# Snake.net
KiCad netlist of a schematic drawn in EAGLE
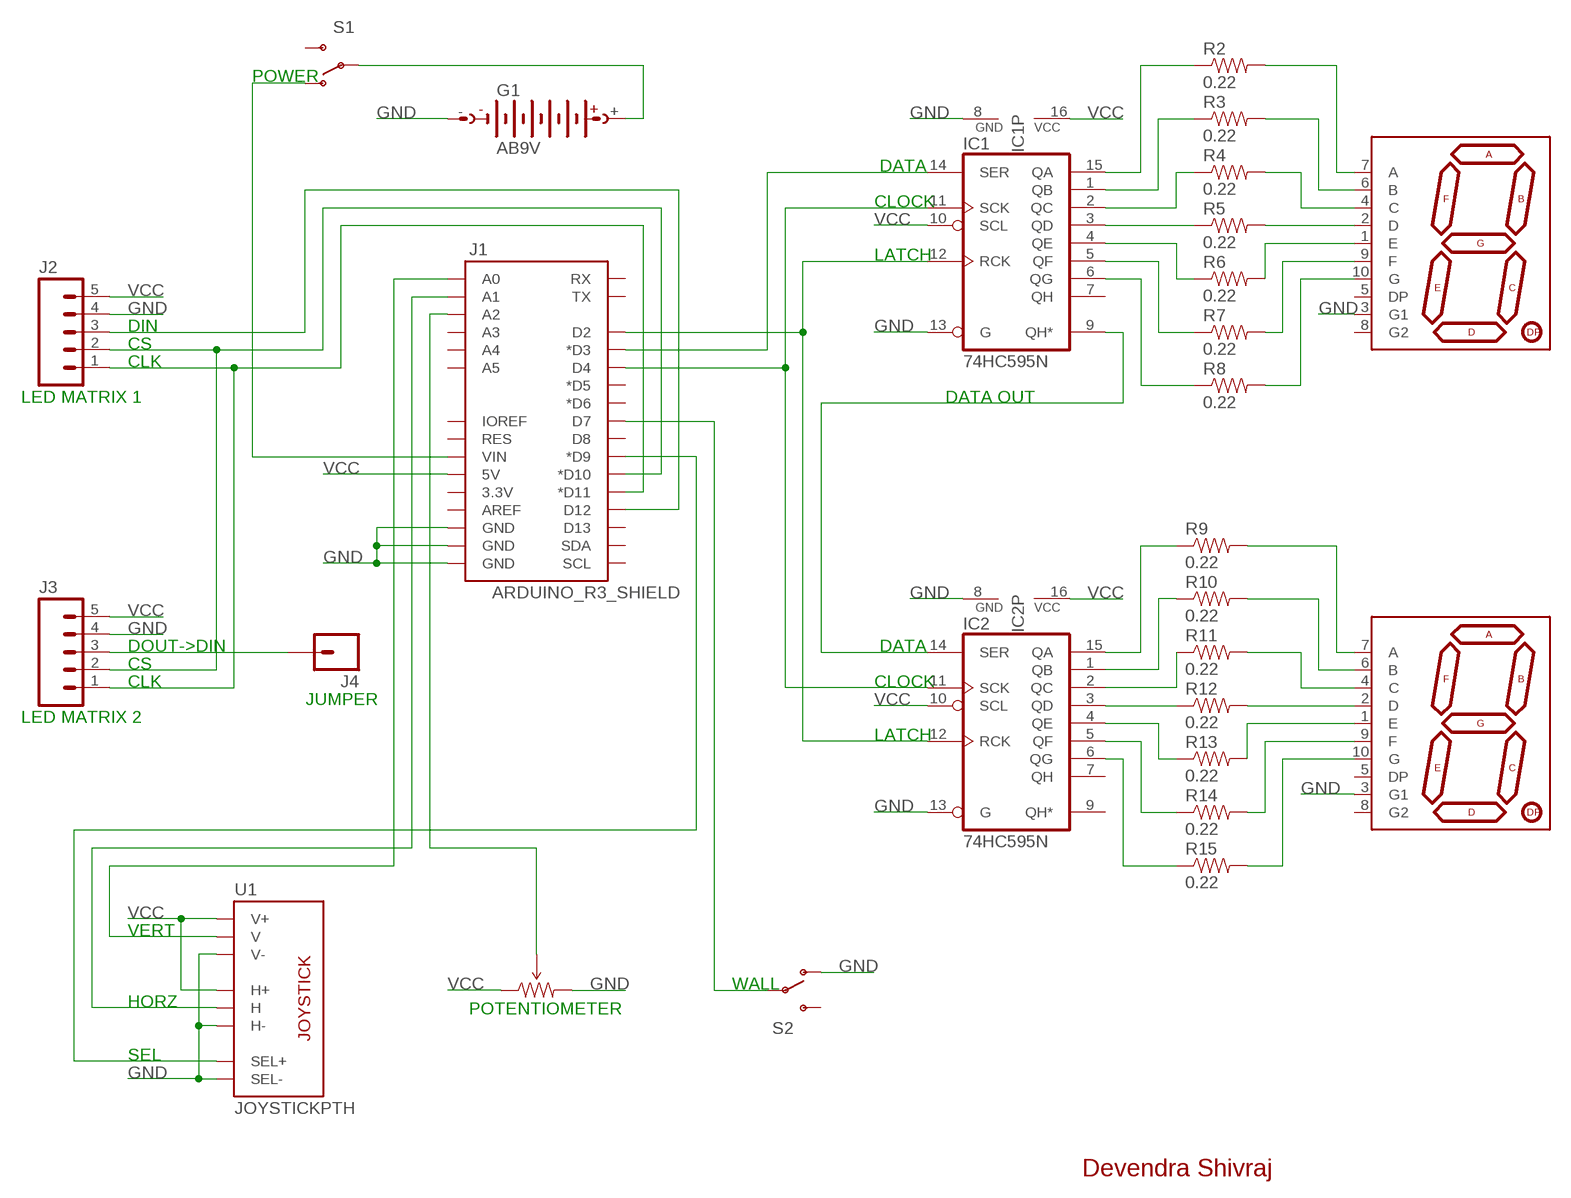
[diagram p0: schematic, sheet 1]

(export (version "E")
  (design (tool "Eeschema 10.0.6"))
  (components
    (comp (ref "G1")
      (value "AB9V")
      (footprint "eagle-import:AB9V")
      (libsource (lib "eagle-import") (part "AB9V"))
    )
    (comp (ref "IC1")
      (value "74HC595N")
      (footprint "eagle-import:DIL16")
      (libsource (lib "eagle-import") (part "74595NHC"))
    )
    (comp (ref "IC2")
      (value "74HC595N")
      (footprint "eagle-import:DIL16")
      (libsource (lib "eagle-import") (part "74595NHC"))
    )
    (comp (ref "J1")
      (value "ARDUINO_R3_SHIELD")
      (footprint "eagle-import:UNO_R3_SHIELD")
      (libsource (lib "eagle-import") (part "ARDUINO_R3_SHIELD"))
    )
    (comp (ref "J2")
      (value "M05PTH")
      (footprint "eagle-import:1X05")
      (libsource (lib "eagle-import") (part "M05PTH"))
    )
    (comp (ref "J3")
      (value "M05PTH")
      (footprint "eagle-import:1X05")
      (libsource (lib "eagle-import") (part "M05PTH"))
    )
    (comp (ref "J4")
      (value "M01PTH")
      (footprint "eagle-import:1X01")
      (libsource (lib "eagle-import") (part "M01PTH"))
    )
    (comp (ref "R1")
      (value "TSR-3386")
      (footprint "eagle-import:3386U")
      (libsource (lib "eagle-import") (part "TRIMPOT-PTH-KNOB"))
    )
    (comp (ref "R2")
      (value "0.22")
      (footprint "eagle-import:0805")
      (libsource (lib "eagle-import") (part "0.22OHM-1/4W-1%(0805)"))
    )
    (comp (ref "R3")
      (value "0.22")
      (footprint "eagle-import:0805")
      (libsource (lib "eagle-import") (part "0.22OHM-1/4W-1%(0805)"))
    )
    (comp (ref "R4")
      (value "0.22")
      (footprint "eagle-import:0805")
      (libsource (lib "eagle-import") (part "0.22OHM-1/4W-1%(0805)"))
    )
    (comp (ref "R5")
      (value "0.22")
      (footprint "eagle-import:0805")
      (libsource (lib "eagle-import") (part "0.22OHM-1/4W-1%(0805)"))
    )
    (comp (ref "R6")
      (value "0.22")
      (footprint "eagle-import:0805")
      (libsource (lib "eagle-import") (part "0.22OHM-1/4W-1%(0805)"))
    )
    (comp (ref "R7")
      (value "0.22")
      (footprint "eagle-import:0805")
      (libsource (lib "eagle-import") (part "0.22OHM-1/4W-1%(0805)"))
    )
    (comp (ref "R8")
      (value "0.22")
      (footprint "eagle-import:0805")
      (libsource (lib "eagle-import") (part "0.22OHM-1/4W-1%(0805)"))
    )
    (comp (ref "R9")
      (value "0.22")
      (footprint "eagle-import:0805")
      (libsource (lib "eagle-import") (part "0.22OHM-1/4W-1%(0805)"))
    )
    (comp (ref "R10")
      (value "0.22")
      (footprint "eagle-import:0805")
      (libsource (lib "eagle-import") (part "0.22OHM-1/4W-1%(0805)"))
    )
    (comp (ref "R11")
      (value "0.22")
      (footprint "eagle-import:0805")
      (libsource (lib "eagle-import") (part "0.22OHM-1/4W-1%(0805)"))
    )
    (comp (ref "R12")
      (value "0.22")
      (footprint "eagle-import:0805")
      (libsource (lib "eagle-import") (part "0.22OHM-1/4W-1%(0805)"))
    )
    (comp (ref "R13")
      (value "0.22")
      (footprint "eagle-import:0805")
      (libsource (lib "eagle-import") (part "0.22OHM-1/4W-1%(0805)"))
    )
    (comp (ref "R14")
      (value "0.22")
      (footprint "eagle-import:0805")
      (libsource (lib "eagle-import") (part "0.22OHM-1/4W-1%(0805)"))
    )
    (comp (ref "R15")
      (value "0.22")
      (footprint "eagle-import:0805")
      (libsource (lib "eagle-import") (part "0.22OHM-1/4W-1%(0805)"))
    )
    (comp (ref "S1")
      (value "SWITCH-SPDTPTH")
      (footprint "eagle-import:SWITCH-SPDT")
      (libsource (lib "eagle-import") (part "SWITCH-SPDTPTH"))
    )
    (comp (ref "S2")
      (value "SWITCH-SPDTPTH")
      (footprint "eagle-import:SWITCH-SPDT")
      (libsource (lib "eagle-import") (part "SWITCH-SPDTPTH"))
    )
    (comp (ref "U$1")
      (value "7-SEGMENT-DISPLAYPTH")
      (footprint "eagle-import:7-SEGMENT-DISPLAY")
      (libsource (lib "eagle-import") (part "7-SEGMENT-DISPLAYPTH"))
    )
    (comp (ref "U$2")
      (value "7-SEGMENT-DISPLAYPTH")
      (footprint "eagle-import:7-SEGMENT-DISPLAY")
      (libsource (lib "eagle-import") (part "7-SEGMENT-DISPLAYPTH"))
    )
    (comp (ref "U1")
      (value "JOYSTICKPTH")
      (footprint "eagle-import:JOYSTICK")
      (libsource (lib "eagle-import") (part "JOYSTICKPTH"))
    )
  )
  (nets
    (net (code "1") (name "/GND") (class "Default")
      (node (ref "G1") (pin "-") (pinfunction "-_-") (pintype "passive"))
      (node (ref "IC1") (pin "13") (pinfunction "G_13") (pintype "input"))
      (node (ref "IC1") (pin "8") (pinfunction "GND_8") (pintype "power_in"))
      (node (ref "IC2") (pin "13") (pinfunction "G_13") (pintype "input"))
      (node (ref "IC2") (pin "8") (pinfunction "GND_8") (pintype "power_in"))
      (node (ref "J1") (pin "GND@0") (pinfunction "GND_GND@0") (pintype "bidirectional"))
      (node (ref "J1") (pin "GND@1") (pinfunction "GND_GND@1") (pintype "bidirectional"))
      (node (ref "J1") (pin "GND@2") (pinfunction "GND_GND@2") (pintype "bidirectional"))
      (node (ref "J2") (pin "4") (pinfunction "4_4") (pintype "passive"))
      (node (ref "J3") (pin "4") (pinfunction "4_4") (pintype "passive"))
      (node (ref "R1") (pin "3") (pinfunction "CW_3") (pintype "passive"))
      (node (ref "S2") (pin "1") (pinfunction "O_1") (pintype "passive"))
      (node (ref "U$1") (pin "3") (pinfunction "G1_3") (pintype "bidirectional"))
      (node (ref "U$2") (pin "3") (pinfunction "G1_3") (pintype "bidirectional"))
      (node (ref "U1") (pin "B2A") (pinfunction "SEL-_B2A") (pintype "bidirectional"))
      (node (ref "U1") (pin "H3") (pinfunction "H-_H3") (pintype "bidirectional"))
      (node (ref "U1") (pin "V3") (pinfunction "V-_V3") (pintype "bidirectional"))
    )
    (net (code "2") (name "/VCC") (class "Default")
      (node (ref "IC1") (pin "10") (pinfunction "SCL_10") (pintype "input"))
      (node (ref "IC1") (pin "16") (pinfunction "VCC_16") (pintype "power_in"))
      (node (ref "IC2") (pin "10") (pinfunction "SCL_10") (pintype "input"))
      (node (ref "IC2") (pin "16") (pinfunction "VCC_16") (pintype "power_in"))
      (node (ref "J1") (pin "5V") (pinfunction "5V_5V") (pintype "bidirectional"))
      (node (ref "J2") (pin "5") (pinfunction "5_5") (pintype "passive"))
      (node (ref "J3") (pin "5") (pinfunction "5_5") (pintype "passive"))
      (node (ref "R1") (pin "1") (pinfunction "CCW_1") (pintype "passive"))
      (node (ref "U1") (pin "H1") (pinfunction "H+_H1") (pintype "bidirectional"))
      (node (ref "U1") (pin "V1") (pinfunction "V+_V1") (pintype "bidirectional"))
    )
    (net (code "3") (name "Net-(IC1A-QA)") (class "Default")
      (node (ref "IC1") (pin "15") (pinfunction "QA_15") (pintype "tri_state"))
      (node (ref "R2") (pin "1") (pinfunction "1_1") (pintype "passive"))
    )
    (net (code "4") (name "Net-(IC1A-QB)") (class "Default")
      (node (ref "IC1") (pin "1") (pinfunction "QB_1") (pintype "tri_state"))
      (node (ref "R3") (pin "1") (pinfunction "1_1") (pintype "passive"))
    )
    (net (code "5") (name "Net-(IC1A-QC)") (class "Default")
      (node (ref "IC1") (pin "2") (pinfunction "QC_2") (pintype "tri_state"))
      (node (ref "R4") (pin "1") (pinfunction "1_1") (pintype "passive"))
    )
    (net (code "6") (name "Net-(IC1A-QD)") (class "Default")
      (node (ref "IC1") (pin "3") (pinfunction "QD_3") (pintype "tri_state"))
      (node (ref "R5") (pin "1") (pinfunction "1_1") (pintype "passive"))
    )
    (net (code "7") (name "Net-(IC1A-QE)") (class "Default")
      (node (ref "IC1") (pin "4") (pinfunction "QE_4") (pintype "tri_state"))
      (node (ref "R6") (pin "1") (pinfunction "1_1") (pintype "passive"))
    )
    (net (code "8") (name "Net-(IC1A-QF)") (class "Default")
      (node (ref "IC1") (pin "5") (pinfunction "QF_5") (pintype "tri_state"))
      (node (ref "R7") (pin "1") (pinfunction "1_1") (pintype "passive"))
    )
    (net (code "9") (name "Net-(IC1A-QG)") (class "Default")
      (node (ref "IC1") (pin "6") (pinfunction "QG_6") (pintype "tri_state"))
      (node (ref "R8") (pin "1") (pinfunction "1_1") (pintype "passive"))
    )
    (net (code "10") (name "Net-(IC1A-QH*)") (class "Default")
      (node (ref "IC1") (pin "9") (pinfunction "QH*_9") (pintype "tri_state"))
      (node (ref "IC2") (pin "14") (pinfunction "SER_14") (pintype "input"))
    )
    (net (code "11") (name "Net-(IC1A-RCK)") (class "Default")
      (node (ref "IC1") (pin "12") (pinfunction "RCK_12") (pintype "input"))
      (node (ref "IC2") (pin "12") (pinfunction "RCK_12") (pintype "input"))
      (node (ref "J1") (pin "D2") (pinfunction "D2_D2") (pintype "bidirectional"))
    )
    (net (code "12") (name "Net-(IC1A-SCK)") (class "Default")
      (node (ref "IC1") (pin "11") (pinfunction "SCK_11") (pintype "input"))
      (node (ref "IC2") (pin "11") (pinfunction "SCK_11") (pintype "input"))
      (node (ref "J1") (pin "D4") (pinfunction "D4_D4") (pintype "bidirectional"))
    )
    (net (code "13") (name "Net-(IC1A-SER)") (class "Default")
      (node (ref "IC1") (pin "14") (pinfunction "SER_14") (pintype "input"))
      (node (ref "J1") (pin "D3") (pinfunction "*D3_D3") (pintype "bidirectional"))
    )
    (net (code "14") (name "Net-(IC2A-QA)") (class "Default")
      (node (ref "IC2") (pin "15") (pinfunction "QA_15") (pintype "tri_state"))
      (node (ref "R9") (pin "1") (pinfunction "1_1") (pintype "passive"))
    )
    (net (code "15") (name "Net-(IC2A-QB)") (class "Default")
      (node (ref "IC2") (pin "1") (pinfunction "QB_1") (pintype "tri_state"))
      (node (ref "R10") (pin "1") (pinfunction "1_1") (pintype "passive"))
    )
    (net (code "16") (name "Net-(IC2A-QC)") (class "Default")
      (node (ref "IC2") (pin "2") (pinfunction "QC_2") (pintype "tri_state"))
      (node (ref "R11") (pin "1") (pinfunction "1_1") (pintype "passive"))
    )
    (net (code "17") (name "Net-(IC2A-QD)") (class "Default")
      (node (ref "IC2") (pin "3") (pinfunction "QD_3") (pintype "tri_state"))
      (node (ref "R12") (pin "1") (pinfunction "1_1") (pintype "passive"))
    )
    (net (code "18") (name "Net-(IC2A-QE)") (class "Default")
      (node (ref "IC2") (pin "4") (pinfunction "QE_4") (pintype "tri_state"))
      (node (ref "R13") (pin "1") (pinfunction "1_1") (pintype "passive"))
    )
    (net (code "19") (name "Net-(IC2A-QF)") (class "Default")
      (node (ref "IC2") (pin "5") (pinfunction "QF_5") (pintype "tri_state"))
      (node (ref "R14") (pin "1") (pinfunction "1_1") (pintype "passive"))
    )
    (net (code "20") (name "Net-(IC2A-QG)") (class "Default")
      (node (ref "IC2") (pin "6") (pinfunction "QG_6") (pintype "tri_state"))
      (node (ref "R15") (pin "1") (pinfunction "1_1") (pintype "passive"))
    )
    (net (code "21") (name "Net-(J1-*D9)") (class "Default")
      (node (ref "J1") (pin "D9") (pinfunction "*D9_D9") (pintype "bidirectional"))
      (node (ref "U1") (pin "B1A") (pinfunction "SEL+_B1A") (pintype "bidirectional"))
    )
    (net (code "22") (name "Net-(J1-*D10)") (class "Default")
      (node (ref "J1") (pin "D10") (pinfunction "*D10_D10") (pintype "bidirectional"))
      (node (ref "J2") (pin "2") (pinfunction "2_2") (pintype "passive"))
      (node (ref "J3") (pin "2") (pinfunction "2_2") (pintype "passive"))
    )
    (net (code "23") (name "Net-(J1-*D11)") (class "Default")
      (node (ref "J1") (pin "D11") (pinfunction "*D11_D11") (pintype "bidirectional"))
      (node (ref "J2") (pin "1") (pinfunction "1_1") (pintype "passive"))
      (node (ref "J3") (pin "1") (pinfunction "1_1") (pintype "passive"))
    )
    (net (code "24") (name "Net-(J1-PadD12)") (class "Default")
      (node (ref "J1") (pin "D12") (pinfunction "D12_D12") (pintype "bidirectional"))
      (node (ref "J2") (pin "3") (pinfunction "3_3") (pintype "passive"))
    )
    (net (code "25") (name "Net-(J3-Pad3)") (class "Default")
      (node (ref "J3") (pin "3") (pinfunction "3_3") (pintype "passive"))
      (node (ref "J4") (pin "1") (pinfunction "1_1") (pintype "passive"))
    )
    (net (code "26") (name "Net-(R1-WIPER)") (class "Default")
      (node (ref "J1") (pin "A2") (pinfunction "A2_A2") (pintype "bidirectional"))
      (node (ref "R1") (pin "2") (pinfunction "WIPER_2") (pintype "passive"))
    )
    (net (code "27") (name "Net-(S1-O)") (class "Default")
      (node (ref "J1") (pin "VIN") (pinfunction "VIN_VIN") (pintype "bidirectional"))
      (node (ref "S1") (pin "1") (pinfunction "O_1") (pintype "passive"))
    )
    (net (code "28") (name "Net-(S1-P)") (class "Default")
      (node (ref "G1") (pin "+") (pinfunction "+_+") (pintype "passive"))
      (node (ref "S1") (pin "2") (pinfunction "P_2") (pintype "passive"))
    )
    (net (code "29") (name "Net-(S2-P)") (class "Default")
      (node (ref "J1") (pin "D7") (pinfunction "D7_D7") (pintype "bidirectional"))
      (node (ref "S2") (pin "2") (pinfunction "P_2") (pintype "passive"))
    )
    (net (code "30") (name "Net-(U$1-A)") (class "Default")
      (node (ref "R2") (pin "2") (pinfunction "2_2") (pintype "passive"))
      (node (ref "U$1") (pin "7") (pinfunction "A_7") (pintype "bidirectional"))
    )
    (net (code "31") (name "Net-(U$1-B)") (class "Default")
      (node (ref "R3") (pin "2") (pinfunction "2_2") (pintype "passive"))
      (node (ref "U$1") (pin "6") (pinfunction "B_6") (pintype "bidirectional"))
    )
    (net (code "32") (name "Net-(U$1-C)") (class "Default")
      (node (ref "R4") (pin "2") (pinfunction "2_2") (pintype "passive"))
      (node (ref "U$1") (pin "4") (pinfunction "C_4") (pintype "bidirectional"))
    )
    (net (code "33") (name "Net-(U$1-D)") (class "Default")
      (node (ref "R5") (pin "2") (pinfunction "2_2") (pintype "passive"))
      (node (ref "U$1") (pin "2") (pinfunction "D_2") (pintype "bidirectional"))
    )
    (net (code "34") (name "Net-(U$1-E)") (class "Default")
      (node (ref "R6") (pin "2") (pinfunction "2_2") (pintype "passive"))
      (node (ref "U$1") (pin "1") (pinfunction "E_1") (pintype "bidirectional"))
    )
    (net (code "35") (name "Net-(U$1-F)") (class "Default")
      (node (ref "R7") (pin "2") (pinfunction "2_2") (pintype "passive"))
      (node (ref "U$1") (pin "9") (pinfunction "F_9") (pintype "bidirectional"))
    )
    (net (code "36") (name "Net-(U$1-G)") (class "Default")
      (node (ref "R8") (pin "2") (pinfunction "2_2") (pintype "passive"))
      (node (ref "U$1") (pin "10") (pinfunction "G_10") (pintype "bidirectional"))
    )
    (net (code "37") (name "Net-(U$2-A)") (class "Default")
      (node (ref "R9") (pin "2") (pinfunction "2_2") (pintype "passive"))
      (node (ref "U$2") (pin "7") (pinfunction "A_7") (pintype "bidirectional"))
    )
    (net (code "38") (name "Net-(U$2-B)") (class "Default")
      (node (ref "R10") (pin "2") (pinfunction "2_2") (pintype "passive"))
      (node (ref "U$2") (pin "6") (pinfunction "B_6") (pintype "bidirectional"))
    )
    (net (code "39") (name "Net-(U$2-C)") (class "Default")
      (node (ref "R11") (pin "2") (pinfunction "2_2") (pintype "passive"))
      (node (ref "U$2") (pin "4") (pinfunction "C_4") (pintype "bidirectional"))
    )
    (net (code "40") (name "Net-(U$2-D)") (class "Default")
      (node (ref "R12") (pin "2") (pinfunction "2_2") (pintype "passive"))
      (node (ref "U$2") (pin "2") (pinfunction "D_2") (pintype "bidirectional"))
    )
    (net (code "41") (name "Net-(U$2-E)") (class "Default")
      (node (ref "R13") (pin "2") (pinfunction "2_2") (pintype "passive"))
      (node (ref "U$2") (pin "1") (pinfunction "E_1") (pintype "bidirectional"))
    )
    (net (code "42") (name "Net-(U$2-F)") (class "Default")
      (node (ref "R14") (pin "2") (pinfunction "2_2") (pintype "passive"))
      (node (ref "U$2") (pin "9") (pinfunction "F_9") (pintype "bidirectional"))
    )
    (net (code "43") (name "Net-(U$2-G)") (class "Default")
      (node (ref "R15") (pin "2") (pinfunction "2_2") (pintype "passive"))
      (node (ref "U$2") (pin "10") (pinfunction "G_10") (pintype "bidirectional"))
    )
    (net (code "44") (name "Net-(U1-H)") (class "Default")
      (node (ref "J1") (pin "A1") (pinfunction "A1_A1") (pintype "bidirectional"))
      (node (ref "U1") (pin "H2") (pinfunction "H_H2") (pintype "bidirectional"))
    )
    (net (code "45") (name "Net-(U1-V)") (class "Default")
      (node (ref "J1") (pin "A0") (pinfunction "A0_A0") (pintype "bidirectional"))
      (node (ref "U1") (pin "V2") (pinfunction "V_V2") (pintype "bidirectional"))
    )
    (net (code "46") (name "unconnected-(IC1A-QH-Pad7)") (class "Default")
      (node (ref "IC1") (pin "7") (pinfunction "QH_7") (pintype "tri_state"))
    )
    (net (code "47") (name "unconnected-(IC2A-QH*-Pad9)") (class "Default")
      (node (ref "IC2") (pin "9") (pinfunction "QH*_9") (pintype "tri_state"))
    )
    (net (code "48") (name "unconnected-(IC2A-QH-Pad7)") (class "Default")
      (node (ref "IC2") (pin "7") (pinfunction "QH_7") (pintype "tri_state"))
    )
    (net (code "49") (name "unconnected-(J1-*D5-PadD5)") (class "Default")
      (node (ref "J1") (pin "D5") (pinfunction "*D5_D5") (pintype "bidirectional"))
    )
    (net (code "50") (name "unconnected-(J1-*D6-PadD6)") (class "Default")
      (node (ref "J1") (pin "D6") (pinfunction "*D6_D6") (pintype "bidirectional"))
    )
    (net (code "51") (name "unconnected-(J1-Pad3.3V)") (class "Default")
      (node (ref "J1") (pin "3.3V") (pinfunction "3.3V_3.3V") (pintype "bidirectional"))
    )
    (net (code "52") (name "unconnected-(J1-PadA3)") (class "Default")
      (node (ref "J1") (pin "A3") (pinfunction "A3_A3") (pintype "bidirectional"))
    )
    (net (code "53") (name "unconnected-(J1-PadA4)") (class "Default")
      (node (ref "J1") (pin "A4") (pinfunction "A4_A4") (pintype "bidirectional"))
    )
    (net (code "54") (name "unconnected-(J1-PadA5)") (class "Default")
      (node (ref "J1") (pin "A5") (pinfunction "A5_A5") (pintype "bidirectional"))
    )
    (net (code "55") (name "unconnected-(J1-PadAREF)") (class "Default")
      (node (ref "J1") (pin "AREF") (pinfunction "AREF_AREF") (pintype "bidirectional"))
    )
    (net (code "56") (name "unconnected-(J1-PadD8)") (class "Default")
      (node (ref "J1") (pin "D8") (pinfunction "D8_D8") (pintype "bidirectional"))
    )
    (net (code "57") (name "unconnected-(J1-PadD13)") (class "Default")
      (node (ref "J1") (pin "D13") (pinfunction "D13_D13") (pintype "bidirectional"))
    )
    (net (code "58") (name "unconnected-(J1-PadIOREF)") (class "Default")
      (node (ref "J1") (pin "IOREF") (pinfunction "IOREF_IOREF") (pintype "bidirectional"))
    )
    (net (code "59") (name "unconnected-(J1-PadRES)") (class "Default")
      (node (ref "J1") (pin "RES") (pinfunction "RES_RES") (pintype "bidirectional"))
    )
    (net (code "60") (name "unconnected-(J1-PadRX)") (class "Default")
      (node (ref "J1") (pin "RX") (pinfunction "RX_RX") (pintype "bidirectional"))
    )
    (net (code "61") (name "unconnected-(J1-PadSCL)") (class "Default")
      (node (ref "J1") (pin "SCL") (pinfunction "SCL_SCL") (pintype "bidirectional"))
    )
    (net (code "62") (name "unconnected-(J1-PadSDA)") (class "Default")
      (node (ref "J1") (pin "SDA") (pinfunction "SDA_SDA") (pintype "bidirectional"))
    )
    (net (code "63") (name "unconnected-(J1-PadTX)") (class "Default")
      (node (ref "J1") (pin "TX") (pinfunction "TX_TX") (pintype "bidirectional"))
    )
    (net (code "64") (name "unconnected-(S1-S-Pad3)") (class "Default")
      (node (ref "S1") (pin "3") (pinfunction "S_3") (pintype "passive"))
    )
    (net (code "65") (name "unconnected-(S2-S-Pad3)") (class "Default")
      (node (ref "S2") (pin "3") (pinfunction "S_3") (pintype "passive"))
    )
    (net (code "66") (name "unconnected-(U$1-DP-Pad5)") (class "Default")
      (node (ref "U$1") (pin "5") (pinfunction "DP_5") (pintype "bidirectional"))
    )
    (net (code "67") (name "unconnected-(U$1-G2-Pad8)") (class "Default")
      (node (ref "U$1") (pin "8") (pinfunction "G2_8") (pintype "bidirectional"))
    )
    (net (code "68") (name "unconnected-(U$2-DP-Pad5)") (class "Default")
      (node (ref "U$2") (pin "5") (pinfunction "DP_5") (pintype "bidirectional"))
    )
    (net (code "69") (name "unconnected-(U$2-G2-Pad8)") (class "Default")
      (node (ref "U$2") (pin "8") (pinfunction "G2_8") (pintype "bidirectional"))
    )
  )
)
